# Generador_De_Retardo.net
KiCad netlist of a schematic drawn in Altium Designer
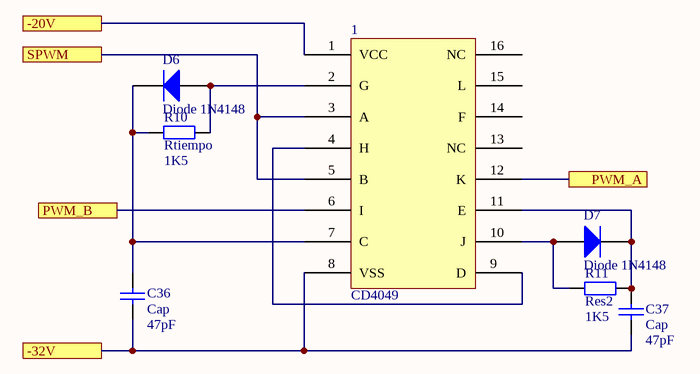
[diagram p0: Generador De Retardo.SchDoc]

(export (version "E")
  (design (tool "Eeschema 10.0.6"))
  (components
    (comp (ref "1") (value "CD4049") (footprint "PDIP16") (libsource (lib "XR2206") (part "CD4049")))
    (comp (ref "C36")
      (value "Cap")
      (footprint "CAP DISCO 200mil")
      (description "Capacitor")
      (fields (field (name "ALTIUM_VALUE") "47pF") (field (name "PUBLISHER") "Altium Limited"))
      (libsource (lib "Miscellaneous Devices") (part "Cap"))
    )
    (comp (ref "C37")
      (value "Cap")
      (footprint "CAP DISCO 200mil")
      (description "Capacitor")
      (fields (field (name "ALTIUM_VALUE") "47pF") (field (name "PUBLISHER") "Altium Limited"))
      (libsource (lib "Miscellaneous Devices") (part "Cap"))
    )
    (comp (ref "D6")
      (value "Diode 1N4148")
      (footprint "SOD323-F")
      (description "High Conductance Fast Diode")
      (fields (field (name "PUBLISHER") "Altium Limited"))
      (libsource (lib "Miscellaneous Devices") (part "Diode 1N4148"))
    )
    (comp (ref "D7")
      (value "Diode 1N4148")
      (footprint "SOD323-F")
      (description "High Conductance Fast Diode")
      (fields (field (name "PUBLISHER") "Altium Limited"))
      (libsource (lib "Miscellaneous Devices") (part "Diode 1N4148"))
    )
    (comp (ref "R10")
      (value "Rtiempo")
      (footprint "1206 resistor")
      (description "Resistor")
      (fields (field (name "ALTIUM_VALUE") "1K5") (field (name "PUBLISHER") "Altium Limited"))
      (libsource (lib "Miscellaneous Devices") (part "Res2"))
    )
    (comp (ref "R11")
      (value "Res2")
      (footprint "1206 resistor")
      (description "Resistor")
      (fields (field (name "ALTIUM_VALUE") "1K5") (field (name "PUBLISHER") "Altium Limited"))
      (libsource (lib "Miscellaneous Devices") (part "Res2"))
    )
  )
  (nets
    (net (code "1") (name "/-20V") (class "Default")
      (node (ref "1") (pin "1") (pinfunction "VCC_1") (pintype "passive"))
    )
    (net (code "2") (name "/-32V") (class "Default")
      (node (ref "1") (pin "8") (pinfunction "VSS_8") (pintype "passive"))
      (node (ref "C36") (pin "1") (pinfunction "1_1") (pintype "passive"))
      (node (ref "C37") (pin "1") (pinfunction "1_1") (pintype "passive"))
    )
    (net (code "3") (name "/PWM_A") (class "Default")
      (node (ref "1") (pin "12") (pinfunction "K_12") (pintype "passive"))
    )
    (net (code "4") (name "/PWM_B") (class "Default")
      (node (ref "1") (pin "6") (pinfunction "I_6") (pintype "passive"))
    )
    (net (code "5") (name "/SPWM") (class "Default")
      (node (ref "1") (pin "3") (pinfunction "A_3") (pintype "passive"))
      (node (ref "1") (pin "5") (pinfunction "B_5") (pintype "passive"))
    )
    (net (code "6") (name "Net-(1-C)") (class "Default")
      (node (ref "1") (pin "7") (pinfunction "C_7") (pintype "passive"))
      (node (ref "C36") (pin "2") (pinfunction "2_2") (pintype "passive"))
      (node (ref "D6") (pin "2") (pinfunction "K_2") (pintype "passive"))
      (node (ref "R10") (pin "1") (pinfunction "1_1") (pintype "passive"))
    )
    (net (code "7") (name "Net-(1-D)") (class "Default")
      (node (ref "1") (pin "4") (pinfunction "H_4") (pintype "passive"))
      (node (ref "1") (pin "9") (pinfunction "D_9") (pintype "passive"))
    )
    (net (code "8") (name "Net-(1-E)") (class "Default")
      (node (ref "1") (pin "11") (pinfunction "E_11") (pintype "passive"))
      (node (ref "C37") (pin "2") (pinfunction "2_2") (pintype "passive"))
      (node (ref "D7") (pin "2") (pinfunction "K_2") (pintype "passive"))
      (node (ref "R11") (pin "2") (pinfunction "2_2") (pintype "passive"))
    )
    (net (code "9") (name "Net-(1-G)") (class "Default")
      (node (ref "1") (pin "2") (pinfunction "G_2") (pintype "passive"))
      (node (ref "D6") (pin "1") (pinfunction "A_1") (pintype "passive"))
      (node (ref "R10") (pin "2") (pinfunction "2_2") (pintype "passive"))
    )
    (net (code "10") (name "Net-(1-J)") (class "Default")
      (node (ref "1") (pin "10") (pinfunction "J_10") (pintype "passive"))
      (node (ref "D7") (pin "1") (pinfunction "A_1") (pintype "passive"))
      (node (ref "R11") (pin "1") (pinfunction "1_1") (pintype "passive"))
    )
    (net (code "11") (name "unconnected-(1-F-Pad14)") (class "Default")
      (node (ref "1") (pin "14") (pinfunction "F_14") (pintype "passive"))
    )
    (net (code "12") (name "unconnected-(1-L-Pad15)") (class "Default")
      (node (ref "1") (pin "15") (pinfunction "L_15") (pintype "passive"))
    )
    (net (code "13") (name "unconnected-(1-NC-Pad13)") (class "Default")
      (node (ref "1") (pin "13") (pinfunction "NC_13") (pintype "passive"))
    )
    (net (code "14") (name "unconnected-(1-NC-Pad16)") (class "Default")
      (node (ref "1") (pin "16") (pinfunction "NC_16") (pintype "passive"))
    )
  )
)
